# MCU.net
KiCad netlist of a schematic drawn in Altium Designer
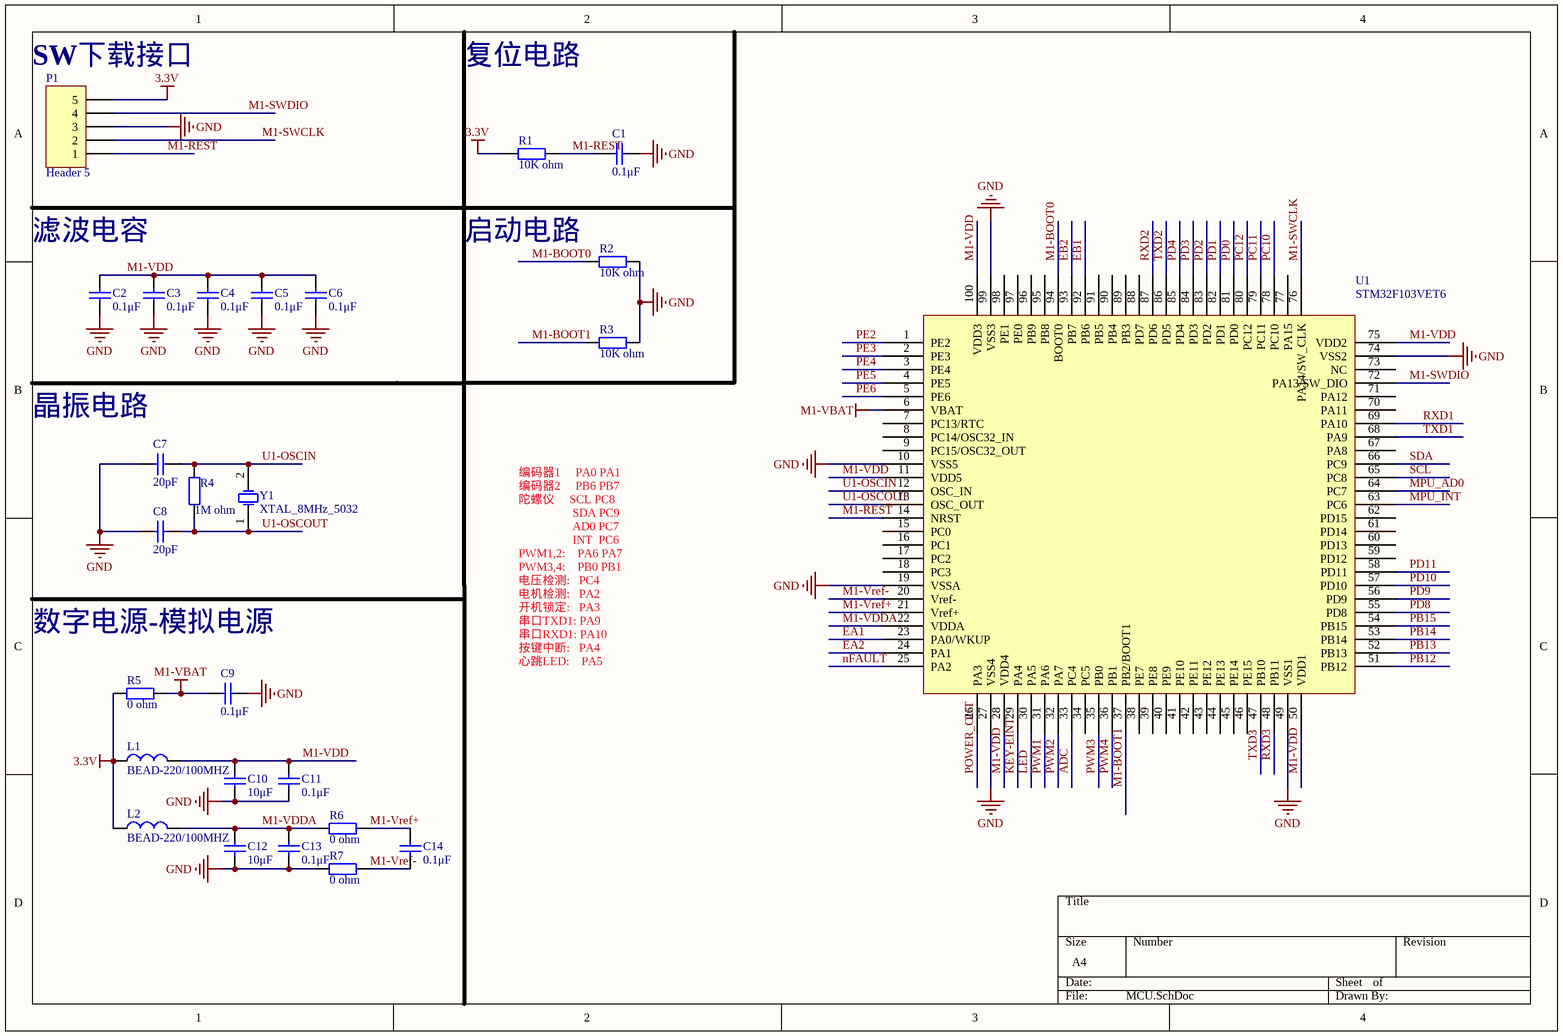
[diagram p0: MCU.SchDoc]

(export (version "E")
  (design (tool "Eeschema 10.0.6"))
  (components
    (comp (ref "C1")
      (value "0.1μF")
      (footprint "Yang_Lib:0603C")
      (description "0.1μF_50V,X7R,±5%")
      (libsource (lib "FSR_BodyLib") (part "Cap_0.1μF_50V_0603"))
    )
    (comp (ref "C2")
      (value "0.1μF")
      (footprint "Yang_Lib:0603C")
      (description "0.1μF_50V,X7R,±5%")
      (libsource (lib "FSR_BodyLib") (part "Cap_0.1μF_50V_0603"))
    )
    (comp (ref "C3")
      (value "0.1μF")
      (footprint "Yang_Lib:0603C")
      (description "0.1μF_50V,X7R,±5%")
      (libsource (lib "FSR_BodyLib") (part "Cap_0.1μF_50V_0603"))
    )
    (comp (ref "C4")
      (value "0.1μF")
      (footprint "Yang_Lib:0603C")
      (description "0.1μF_50V,X7R,±5%")
      (libsource (lib "FSR_BodyLib") (part "Cap_0.1μF_50V_0603"))
    )
    (comp (ref "C5")
      (value "0.1μF")
      (footprint "Yang_Lib:0603C")
      (description "0.1μF_50V,X7R,±5%")
      (libsource (lib "FSR_BodyLib") (part "Cap_0.1μF_50V_0603"))
    )
    (comp (ref "C6")
      (value "0.1μF")
      (footprint "Yang_Lib:0603C")
      (description "0.1μF_50V,X7R,±5%")
      (libsource (lib "FSR_BodyLib") (part "Cap_0.1μF_50V_0603"))
    )
    (comp (ref "C7")
      (value "20pF")
      (footprint "Yang_Lib:0603C")
      (description "20pF_50V,CH,±5%")
      (libsource (lib "FSR_BodyLib") (part "Cap_20pF_50V_0603"))
    )
    (comp (ref "C8")
      (value "20pF")
      (footprint "Yang_Lib:0603C")
      (description "20pF_50V,CH,±5%")
      (libsource (lib "FSR_BodyLib") (part "Cap_20pF_50V_0603"))
    )
    (comp (ref "C9")
      (value "0.1μF")
      (footprint "Yang_Lib:0603C")
      (description "0.1μF_50V,X7R,±5%")
      (libsource (lib "FSR_BodyLib") (part "Cap_0.1μF_50V_0603"))
    )
    (comp (ref "C10")
      (value "10μF")
      (footprint "Yang_Lib:0603C")
      (description "10μF_35V,X5R,20%")
      (libsource (lib "FSR_BodyLib") (part "Cap_10μF_35V_0603"))
    )
    (comp (ref "C11")
      (value "0.1μF")
      (footprint "Yang_Lib:0603C")
      (description "0.1μF_50V,X7R,±5%")
      (libsource (lib "FSR_BodyLib") (part "Cap_0.1μF_50V_0603"))
    )
    (comp (ref "C12")
      (value "10μF")
      (footprint "Yang_Lib:0603C")
      (description "10μF_35V,X5R,20%")
      (libsource (lib "FSR_BodyLib") (part "Cap_10μF_35V_0603"))
    )
    (comp (ref "C13")
      (value "0.1μF")
      (footprint "Yang_Lib:0603C")
      (description "0.1μF_50V,X7R,±5%")
      (libsource (lib "FSR_BodyLib") (part "Cap_0.1μF_50V_0603"))
    )
    (comp (ref "C14")
      (value "0.1μF")
      (footprint "Yang_Lib:0603C")
      (description "0.1μF_50V,X7R,±5%")
      (libsource (lib "FSR_BodyLib") (part "Cap_0.1μF_50V_0603"))
    )
    (comp (ref "L1")
      (value "BEAD-220/100MHZ")
      (footprint "Yang_Lib:0603R")
      (libsource (lib "FSR_BodyLib") (part "BEAD-220/100MHZ_0603"))
    )
    (comp (ref "L2")
      (value "BEAD-220/100MHZ")
      (footprint "Yang_Lib:0603R")
      (libsource (lib "FSR_BodyLib") (part "BEAD-220/100MHZ_0603"))
    )
    (comp (ref "P1")
      (value "Header 5")
      (footprint "HDR1X5")
      (description "Header, 5-Pin")
      (fields (field (name "PUBLISHER") "Altium Limited"))
      (libsource (lib "Miscellaneous Connectors") (part "Header 5"))
    )
    (comp (ref "R1")
      (value "10K ohm")
      (footprint "Yang_Lib:0603R")
      (description "10K ohm,1%")
      (libsource (lib "FSR_BodyLib") (part "Res_10K ohm_0603"))
    )
    (comp (ref "R2")
      (value "10K ohm")
      (footprint "Yang_Lib:0603R")
      (description "10K ohm,1%")
      (libsource (lib "FSR_BodyLib") (part "Res_10K ohm_0603"))
    )
    (comp (ref "R3")
      (value "10K ohm")
      (footprint "Yang_Lib:0603R")
      (description "10K ohm,1%")
      (libsource (lib "FSR_BodyLib") (part "Res_10K ohm_0603"))
    )
    (comp (ref "R4")
      (value "1M ohm")
      (footprint "Yang_Lib:0603R")
      (description "1M ohm,1%")
      (libsource (lib "FSR_BodyLib") (part "Res_1M ohm_0603"))
    )
    (comp (ref "R5")
      (value "0 ohm")
      (footprint "Yang_Lib:0603R")
      (description "0 ohm,5%")
      (libsource (lib "FSR_BodyLib") (part "Res_0 ohm_0603"))
    )
    (comp (ref "R6")
      (value "0 ohm")
      (footprint "Yang_Lib:0603R")
      (description "0 ohm,5%")
      (libsource (lib "FSR_BodyLib") (part "Res_0 ohm_0603"))
    )
    (comp (ref "R7")
      (value "0 ohm")
      (footprint "Yang_Lib:0603R")
      (description "0 ohm,5%")
      (libsource (lib "FSR_BodyLib") (part "Res_0 ohm_0603"))
    )
    (comp (ref "U1")
      (value "STM32F103VET6")
      (footprint "Yang_Lib:LQFP100")
      (libsource (lib "FSR_BodyLib") (part "STM32F103VET6"))
    )
    (comp (ref "Y1")
      (value "XTAL_8MHz_5032")
      (footprint "5032")
      (description "XTAL_8MHz")
      (libsource (lib "Yang_Lib") (part "XTAL_8MHz_5032"))
    )
  )
  (nets
    (net (code "1") (name "/ADC") (class "Default")
      (node (ref "U1") (pin "33") (pinfunction "PC4_33") (pintype "passive"))
    )
    (net (code "2") (name "/EA1") (class "Default")
      (node (ref "U1") (pin "23") (pinfunction "PA0/WKUP_23") (pintype "passive"))
    )
    (net (code "3") (name "/EA2") (class "Default")
      (node (ref "U1") (pin "24") (pinfunction "PA1_24") (pintype "passive"))
    )
    (net (code "4") (name "/EB1") (class "Default")
      (node (ref "U1") (pin "92") (pinfunction "PB6_92") (pintype "passive"))
    )
    (net (code "5") (name "/EB2") (class "Default")
      (node (ref "U1") (pin "93") (pinfunction "PB7_93") (pintype "passive"))
    )
    (net (code "6") (name "/KEY-EINT") (class "Default")
      (node (ref "U1") (pin "29") (pinfunction "PA4_29") (pintype "passive"))
    )
    (net (code "7") (name "/LED") (class "Default")
      (node (ref "U1") (pin "30") (pinfunction "PA5_30") (pintype "passive"))
    )
    (net (code "8") (name "/M1-BOOT0") (class "Default")
      (node (ref "R2") (pin "1") (pinfunction "1_1") (pintype "passive"))
      (node (ref "U1") (pin "94") (pinfunction "BOOT0_94") (pintype "passive"))
    )
    (net (code "9") (name "/M1-BOOT1") (class "Default")
      (node (ref "R3") (pin "1") (pinfunction "1_1") (pintype "passive"))
      (node (ref "U1") (pin "37") (pinfunction "PB2/BOOT1_37") (pintype "passive"))
    )
    (net (code "10") (name "/M1-REST") (class "Default")
      (node (ref "C1") (pin "1") (pinfunction "1_1") (pintype "passive"))
      (node (ref "P1") (pin "1") (pinfunction "1_1") (pintype "passive"))
      (node (ref "R1") (pin "2") (pinfunction "2_2") (pintype "passive"))
      (node (ref "U1") (pin "14") (pinfunction "NRST_14") (pintype "passive"))
    )
    (net (code "11") (name "/M1-SWCLK") (class "Default")
      (node (ref "P1") (pin "2") (pinfunction "2_2") (pintype "passive"))
      (node (ref "U1") (pin "76") (pinfunction "PA14/SW_CLK_76") (pintype "passive"))
    )
    (net (code "12") (name "/M1-SWDIO") (class "Default")
      (node (ref "P1") (pin "4") (pinfunction "4_4") (pintype "passive"))
      (node (ref "U1") (pin "72") (pinfunction "PA13/SW_DIO_72") (pintype "passive"))
    )
    (net (code "13") (name "/M1-VDD") (class "Default")
      (node (ref "C10") (pin "2") (pinfunction "2_2") (pintype "passive"))
      (node (ref "C11") (pin "2") (pinfunction "2_2") (pintype "passive"))
      (node (ref "C2") (pin "2") (pinfunction "2_2") (pintype "passive"))
      (node (ref "C3") (pin "2") (pinfunction "2_2") (pintype "passive"))
      (node (ref "C4") (pin "2") (pinfunction "2_2") (pintype "passive"))
      (node (ref "C5") (pin "2") (pinfunction "2_2") (pintype "passive"))
      (node (ref "C6") (pin "2") (pinfunction "2_2") (pintype "passive"))
      (node (ref "L1") (pin "2") (pinfunction "2_2") (pintype "passive"))
      (node (ref "U1") (pin "100") (pinfunction "VDD3_100") (pintype "passive"))
      (node (ref "U1") (pin "11") (pinfunction "VDD5_11") (pintype "passive"))
      (node (ref "U1") (pin "28") (pinfunction "VDD4_28") (pintype "passive"))
      (node (ref "U1") (pin "50") (pinfunction "VDD1_50") (pintype "passive"))
      (node (ref "U1") (pin "75") (pinfunction "VDD2_75") (pintype "passive"))
    )
    (net (code "14") (name "/M1-VDDA") (class "Default")
      (node (ref "C12") (pin "2") (pinfunction "2_2") (pintype "passive"))
      (node (ref "C13") (pin "2") (pinfunction "2_2") (pintype "passive"))
      (node (ref "L2") (pin "2") (pinfunction "2_2") (pintype "passive"))
      (node (ref "R6") (pin "1") (pinfunction "1_1") (pintype "passive"))
      (node (ref "U1") (pin "22") (pinfunction "VDDA_22") (pintype "passive"))
    )
    (net (code "15") (name "/M1-Vref+") (class "Default")
      (node (ref "C14") (pin "2") (pinfunction "2_2") (pintype "passive"))
      (node (ref "R6") (pin "2") (pinfunction "2_2") (pintype "passive"))
      (node (ref "U1") (pin "21") (pinfunction "Vref+_21") (pintype "passive"))
    )
    (net (code "16") (name "/M1-Vref-") (class "Default")
      (node (ref "C14") (pin "1") (pinfunction "1_1") (pintype "passive"))
      (node (ref "R7") (pin "2") (pinfunction "2_2") (pintype "passive"))
      (node (ref "U1") (pin "20") (pinfunction "Vref-_20") (pintype "passive"))
    )
    (net (code "17") (name "/MPU_AD0") (class "Default")
      (node (ref "U1") (pin "64") (pinfunction "PC7_64") (pintype "passive"))
    )
    (net (code "18") (name "/MPU_INT") (class "Default")
      (node (ref "U1") (pin "63") (pinfunction "PC6_63") (pintype "passive"))
    )
    (net (code "19") (name "/PB12") (class "Default")
      (node (ref "U1") (pin "51") (pinfunction "PB12_51") (pintype "passive"))
    )
    (net (code "20") (name "/PB13") (class "Default")
      (node (ref "U1") (pin "52") (pinfunction "PB13_52") (pintype "passive"))
    )
    (net (code "21") (name "/PB14") (class "Default")
      (node (ref "U1") (pin "53") (pinfunction "PB14_53") (pintype "passive"))
    )
    (net (code "22") (name "/PB15") (class "Default")
      (node (ref "U1") (pin "54") (pinfunction "PB15_54") (pintype "passive"))
    )
    (net (code "23") (name "/PC10") (class "Default")
      (node (ref "U1") (pin "78") (pinfunction "PC10_78") (pintype "passive"))
    )
    (net (code "24") (name "/PC11") (class "Default")
      (node (ref "U1") (pin "79") (pinfunction "PC11_79") (pintype "passive"))
    )
    (net (code "25") (name "/PC12") (class "Default")
      (node (ref "U1") (pin "80") (pinfunction "PC12_80") (pintype "passive"))
    )
    (net (code "26") (name "/PD0") (class "Default")
      (node (ref "U1") (pin "81") (pinfunction "PD0_81") (pintype "passive"))
    )
    (net (code "27") (name "/PD1") (class "Default")
      (node (ref "U1") (pin "82") (pinfunction "PD1_82") (pintype "passive"))
    )
    (net (code "28") (name "/PD2") (class "Default")
      (node (ref "U1") (pin "83") (pinfunction "PD2_83") (pintype "passive"))
    )
    (net (code "29") (name "/PD3") (class "Default")
      (node (ref "U1") (pin "84") (pinfunction "PD3_84") (pintype "passive"))
    )
    (net (code "30") (name "/PD4") (class "Default")
      (node (ref "U1") (pin "85") (pinfunction "PD4_85") (pintype "passive"))
    )
    (net (code "31") (name "/PD8") (class "Default")
      (node (ref "U1") (pin "55") (pinfunction "PD8_55") (pintype "passive"))
    )
    (net (code "32") (name "/PD9") (class "Default")
      (node (ref "U1") (pin "56") (pinfunction "PD9_56") (pintype "passive"))
    )
    (net (code "33") (name "/PD10") (class "Default")
      (node (ref "U1") (pin "57") (pinfunction "PD10_57") (pintype "passive"))
    )
    (net (code "34") (name "/PD11") (class "Default")
      (node (ref "U1") (pin "58") (pinfunction "PD11_58") (pintype "passive"))
    )
    (net (code "35") (name "/PE2") (class "Default")
      (node (ref "U1") (pin "1") (pinfunction "PE2_1") (pintype "passive"))
    )
    (net (code "36") (name "/PE3") (class "Default")
      (node (ref "U1") (pin "2") (pinfunction "PE3_2") (pintype "passive"))
    )
    (net (code "37") (name "/PE4") (class "Default")
      (node (ref "U1") (pin "3") (pinfunction "PE4_3") (pintype "passive"))
    )
    (net (code "38") (name "/PE5") (class "Default")
      (node (ref "U1") (pin "4") (pinfunction "PE5_4") (pintype "passive"))
    )
    (net (code "39") (name "/PE6") (class "Default")
      (node (ref "U1") (pin "5") (pinfunction "PE6_5") (pintype "passive"))
    )
    (net (code "40") (name "/POWER_OUT") (class "Default")
      (node (ref "U1") (pin "26") (pinfunction "PA3_26") (pintype "passive"))
    )
    (net (code "41") (name "/PWM1") (class "Default")
      (node (ref "U1") (pin "31") (pinfunction "PA6_31") (pintype "passive"))
    )
    (net (code "42") (name "/PWM2") (class "Default")
      (node (ref "U1") (pin "32") (pinfunction "PA7_32") (pintype "passive"))
    )
    (net (code "43") (name "/PWM3") (class "Default")
      (node (ref "U1") (pin "35") (pinfunction "PB0_35") (pintype "passive"))
    )
    (net (code "44") (name "/PWM4") (class "Default")
      (node (ref "U1") (pin "36") (pinfunction "PB1_36") (pintype "passive"))
    )
    (net (code "45") (name "/RXD1") (class "Default")
      (node (ref "U1") (pin "69") (pinfunction "PA10_69") (pintype "passive"))
    )
    (net (code "46") (name "/RXD2") (class "Default")
      (node (ref "U1") (pin "87") (pinfunction "PD6_87") (pintype "passive"))
    )
    (net (code "47") (name "/RXD3") (class "Default")
      (node (ref "U1") (pin "48") (pinfunction "PB11_48") (pintype "passive"))
    )
    (net (code "48") (name "/SCL") (class "Default")
      (node (ref "U1") (pin "65") (pinfunction "PC8_65") (pintype "passive"))
    )
    (net (code "49") (name "/SDA") (class "Default")
      (node (ref "U1") (pin "66") (pinfunction "PC9_66") (pintype "passive"))
    )
    (net (code "50") (name "/TXD1") (class "Default")
      (node (ref "U1") (pin "68") (pinfunction "PA9_68") (pintype "passive"))
    )
    (net (code "51") (name "/TXD2") (class "Default")
      (node (ref "U1") (pin "86") (pinfunction "PD5_86") (pintype "passive"))
    )
    (net (code "52") (name "/TXD3") (class "Default")
      (node (ref "U1") (pin "47") (pinfunction "PB10_47") (pintype "passive"))
    )
    (net (code "53") (name "/U1-OSCIN") (class "Default")
      (node (ref "C7") (pin "2") (pinfunction "2_2") (pintype "passive"))
      (node (ref "R4") (pin "2") (pinfunction "2_2") (pintype "passive"))
      (node (ref "U1") (pin "12") (pinfunction "OSC_IN_12") (pintype "passive"))
      (node (ref "Y1") (pin "2") (pinfunction "OSC2_2") (pintype "passive"))
    )
    (net (code "54") (name "/U1-OSCOUT") (class "Default")
      (node (ref "C8") (pin "2") (pinfunction "2_2") (pintype "passive"))
      (node (ref "R4") (pin "1") (pinfunction "1_1") (pintype "passive"))
      (node (ref "U1") (pin "13") (pinfunction "OSC_OUT_13") (pintype "passive"))
      (node (ref "Y1") (pin "1") (pinfunction "OSC1_1") (pintype "passive"))
    )
    (net (code "55") (name "/nFAULT") (class "Default")
      (node (ref "U1") (pin "25") (pinfunction "PA2_25") (pintype "passive"))
    )
    (net (code "56") (name "3.3V") (class "Default")
      (node (ref "L1") (pin "1") (pinfunction "1_1") (pintype "passive"))
      (node (ref "L2") (pin "1") (pinfunction "1_1") (pintype "passive"))
      (node (ref "P1") (pin "5") (pinfunction "5_5") (pintype "passive"))
      (node (ref "R1") (pin "1") (pinfunction "1_1") (pintype "passive"))
      (node (ref "R5") (pin "1") (pinfunction "1_1") (pintype "passive"))
    )
    (net (code "57") (name "GND") (class "Default")
      (node (ref "C1") (pin "2") (pinfunction "2_2") (pintype "passive"))
      (node (ref "C10") (pin "1") (pinfunction "1_1") (pintype "passive"))
      (node (ref "C11") (pin "1") (pinfunction "1_1") (pintype "passive"))
      (node (ref "C12") (pin "1") (pinfunction "1_1") (pintype "passive"))
      (node (ref "C13") (pin "1") (pinfunction "1_1") (pintype "passive"))
      (node (ref "C2") (pin "1") (pinfunction "1_1") (pintype "passive"))
      (node (ref "C3") (pin "1") (pinfunction "1_1") (pintype "passive"))
      (node (ref "C4") (pin "1") (pinfunction "1_1") (pintype "passive"))
      (node (ref "C5") (pin "1") (pinfunction "1_1") (pintype "passive"))
      (node (ref "C6") (pin "1") (pinfunction "1_1") (pintype "passive"))
      (node (ref "C7") (pin "1") (pinfunction "1_1") (pintype "passive"))
      (node (ref "C8") (pin "1") (pinfunction "1_1") (pintype "passive"))
      (node (ref "C9") (pin "1") (pinfunction "1_1") (pintype "passive"))
      (node (ref "P1") (pin "3") (pinfunction "3_3") (pintype "passive"))
      (node (ref "R2") (pin "2") (pinfunction "2_2") (pintype "passive"))
      (node (ref "R3") (pin "2") (pinfunction "2_2") (pintype "passive"))
      (node (ref "R7") (pin "1") (pinfunction "1_1") (pintype "passive"))
      (node (ref "U1") (pin "10") (pinfunction "VSS5_10") (pintype "passive"))
      (node (ref "U1") (pin "19") (pinfunction "VSSA_19") (pintype "passive"))
      (node (ref "U1") (pin "27") (pinfunction "VSS4_27") (pintype "passive"))
      (node (ref "U1") (pin "49") (pinfunction "VSS1_49") (pintype "passive"))
      (node (ref "U1") (pin "74") (pinfunction "VSS2_74") (pintype "passive"))
      (node (ref "U1") (pin "99") (pinfunction "VSS3_99") (pintype "passive"))
    )
    (net (code "58") (name "M1-VBAT") (class "Default")
      (node (ref "C9") (pin "2") (pinfunction "2_2") (pintype "passive"))
      (node (ref "R5") (pin "2") (pinfunction "2_2") (pintype "passive"))
      (node (ref "U1") (pin "6") (pinfunction "VBAT_6") (pintype "passive"))
    )
    (net (code "59") (name "unconnected-(U1-NC-Pad73)") (class "Default")
      (node (ref "U1") (pin "73") (pinfunction "NC_73") (pintype "passive"))
    )
    (net (code "60") (name "unconnected-(U1-PA8-Pad67)") (class "Default")
      (node (ref "U1") (pin "67") (pinfunction "PA8_67") (pintype "passive"))
    )
    (net (code "61") (name "unconnected-(U1-PA11-Pad70)") (class "Default")
      (node (ref "U1") (pin "70") (pinfunction "PA11_70") (pintype "passive"))
    )
    (net (code "62") (name "unconnected-(U1-PA12-Pad71)") (class "Default")
      (node (ref "U1") (pin "71") (pinfunction "PA12_71") (pintype "passive"))
    )
    (net (code "63") (name "unconnected-(U1-PA15-Pad77)") (class "Default")
      (node (ref "U1") (pin "77") (pinfunction "PA15_77") (pintype "passive"))
    )
    (net (code "64") (name "unconnected-(U1-PB3-Pad89)") (class "Default")
      (node (ref "U1") (pin "89") (pinfunction "PB3_89") (pintype "passive"))
    )
    (net (code "65") (name "unconnected-(U1-PB4-Pad90)") (class "Default")
      (node (ref "U1") (pin "90") (pinfunction "PB4_90") (pintype "passive"))
    )
    (net (code "66") (name "unconnected-(U1-PB5-Pad91)") (class "Default")
      (node (ref "U1") (pin "91") (pinfunction "PB5_91") (pintype "passive"))
    )
    (net (code "67") (name "unconnected-(U1-PB8-Pad95)") (class "Default")
      (node (ref "U1") (pin "95") (pinfunction "PB8_95") (pintype "passive"))
    )
    (net (code "68") (name "unconnected-(U1-PB9-Pad96)") (class "Default")
      (node (ref "U1") (pin "96") (pinfunction "PB9_96") (pintype "passive"))
    )
    (net (code "69") (name "unconnected-(U1-PC0-Pad15)") (class "Default")
      (node (ref "U1") (pin "15") (pinfunction "PC0_15") (pintype "passive"))
    )
    (net (code "70") (name "unconnected-(U1-PC1-Pad16)") (class "Default")
      (node (ref "U1") (pin "16") (pinfunction "PC1_16") (pintype "passive"))
    )
    (net (code "71") (name "unconnected-(U1-PC2-Pad17)") (class "Default")
      (node (ref "U1") (pin "17") (pinfunction "PC2_17") (pintype "passive"))
    )
    (net (code "72") (name "unconnected-(U1-PC3-Pad18)") (class "Default")
      (node (ref "U1") (pin "18") (pinfunction "PC3_18") (pintype "passive"))
    )
    (net (code "73") (name "unconnected-(U1-PC5-Pad34)") (class "Default")
      (node (ref "U1") (pin "34") (pinfunction "PC5_34") (pintype "passive"))
    )
    (net (code "74") (name "unconnected-(U1-PC13{slash}RTC-Pad7)") (class "Default")
      (node (ref "U1") (pin "7") (pinfunction "PC13/RTC_7") (pintype "passive"))
    )
    (net (code "75") (name "unconnected-(U1-PC14{slash}OSC32_IN-Pad8)") (class "Default")
      (node (ref "U1") (pin "8") (pinfunction "PC14/OSC32_IN_8") (pintype "passive"))
    )
    (net (code "76") (name "unconnected-(U1-PC15{slash}OSC32_OUT-Pad9)") (class "Default")
      (node (ref "U1") (pin "9") (pinfunction "PC15/OSC32_OUT_9") (pintype "passive"))
    )
    (net (code "77") (name "unconnected-(U1-PD7-Pad88)") (class "Default")
      (node (ref "U1") (pin "88") (pinfunction "PD7_88") (pintype "passive"))
    )
    (net (code "78") (name "unconnected-(U1-PD12-Pad59)") (class "Default")
      (node (ref "U1") (pin "59") (pinfunction "PD12_59") (pintype "passive"))
    )
    (net (code "79") (name "unconnected-(U1-PD13-Pad60)") (class "Default")
      (node (ref "U1") (pin "60") (pinfunction "PD13_60") (pintype "passive"))
    )
    (net (code "80") (name "unconnected-(U1-PD14-Pad61)") (class "Default")
      (node (ref "U1") (pin "61") (pinfunction "PD14_61") (pintype "passive"))
    )
    (net (code "81") (name "unconnected-(U1-PD15-Pad62)") (class "Default")
      (node (ref "U1") (pin "62") (pinfunction "PD15_62") (pintype "passive"))
    )
    (net (code "82") (name "unconnected-(U1-PE0-Pad97)") (class "Default")
      (node (ref "U1") (pin "97") (pinfunction "PE0_97") (pintype "passive"))
    )
    (net (code "83") (name "unconnected-(U1-PE1-Pad98)") (class "Default")
      (node (ref "U1") (pin "98") (pinfunction "PE1_98") (pintype "passive"))
    )
    (net (code "84") (name "unconnected-(U1-PE7-Pad38)") (class "Default")
      (node (ref "U1") (pin "38") (pinfunction "PE7_38") (pintype "passive"))
    )
    (net (code "85") (name "unconnected-(U1-PE8-Pad39)") (class "Default")
      (node (ref "U1") (pin "39") (pinfunction "PE8_39") (pintype "passive"))
    )
    (net (code "86") (name "unconnected-(U1-PE9-Pad40)") (class "Default")
      (node (ref "U1") (pin "40") (pinfunction "PE9_40") (pintype "passive"))
    )
    (net (code "87") (name "unconnected-(U1-PE10-Pad41)") (class "Default")
      (node (ref "U1") (pin "41") (pinfunction "PE10_41") (pintype "passive"))
    )
    (net (code "88") (name "unconnected-(U1-PE11-Pad42)") (class "Default")
      (node (ref "U1") (pin "42") (pinfunction "PE11_42") (pintype "passive"))
    )
    (net (code "89") (name "unconnected-(U1-PE12-Pad43)") (class "Default")
      (node (ref "U1") (pin "43") (pinfunction "PE12_43") (pintype "passive"))
    )
    (net (code "90") (name "unconnected-(U1-PE13-Pad44)") (class "Default")
      (node (ref "U1") (pin "44") (pinfunction "PE13_44") (pintype "passive"))
    )
    (net (code "91") (name "unconnected-(U1-PE14-Pad45)") (class "Default")
      (node (ref "U1") (pin "45") (pinfunction "PE14_45") (pintype "passive"))
    )
    (net (code "92") (name "unconnected-(U1-PE15-Pad46)") (class "Default")
      (node (ref "U1") (pin "46") (pinfunction "PE15_46") (pintype "passive"))
    )
  )
)
